# Sheet2.net
KiCad netlist of a schematic drawn in Altium Designer
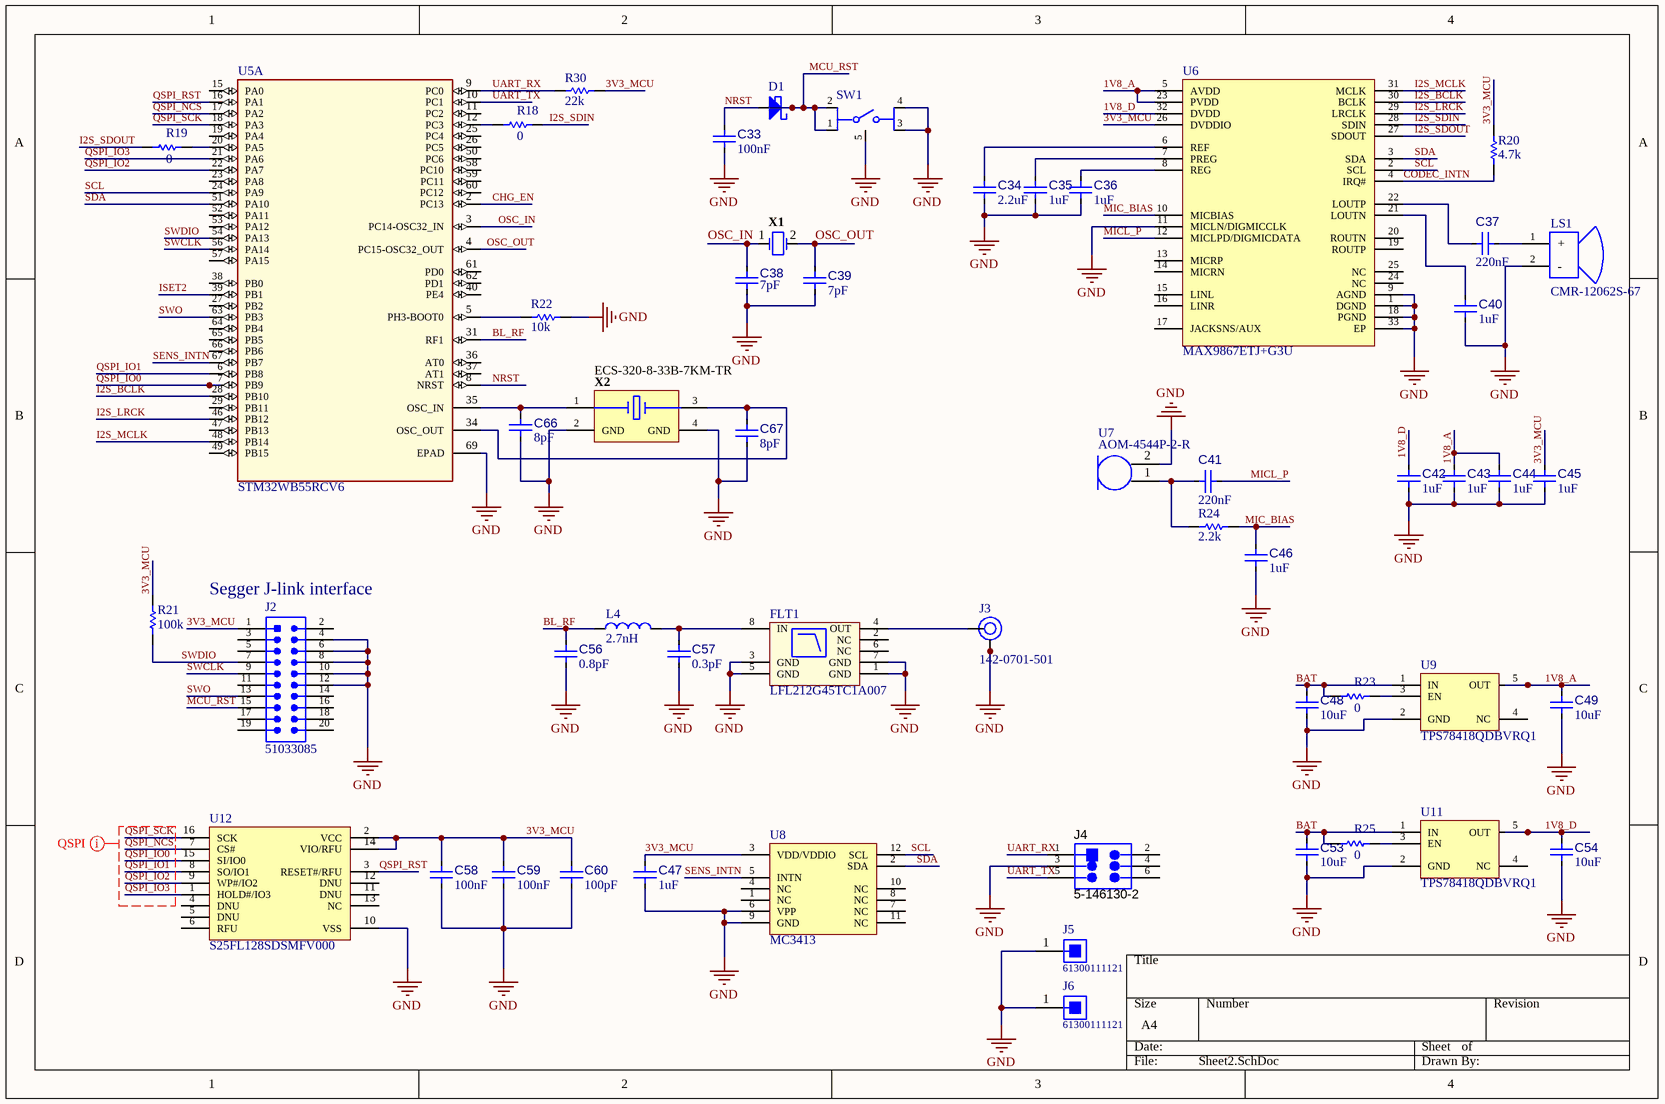
[diagram p0: Sheet2.SchDoc]

(export (version "E")
  (design (tool "Eeschema 10.0.6"))
  (components
    (comp (ref "C33")
      (value "100nF")
      (footprint "0402-SMD-CAP")
      (description "Chip Capacitor, 0.1 uF, +/- 5%, 16 V, 0402 (1005 Metric)")
      (fields (field (name "TOLERANCE") "5%") (field (name "MFR. PART NO.") "EMF105B7104MVHF"))
      (libsource (lib "Budapest University of Technology and Economics") (part "CAP-NP-2"))
    )
    (comp (ref "C34")
      (value "2.2uF")
      (footprint "0603-SMD-CAP")
      (description "CAP CER 2.2UF 10V X7R 0603")
      (fields (field (name "TOLERANCE") "10%") (field (name "VOLTAGE") "10V"))
      (libsource (lib "Budapest University of Technology and Economics") (part "CAP-NP-2"))
    )
    (comp (ref "C35")
      (value "1uF")
      (footprint "0603-SMD-CAP")
      (fields
        (field (name "VOLTAGE") "25V")
        (field (name "TOLERANCE") "10%")
        (field (name "MFR. PART NO.") "C0603C105K3PACTU")
      )
      (libsource (lib "Budapest University of Technology and Economics") (part "CAP-NP-2"))
    )
    (comp (ref "C36")
      (value "1uF")
      (footprint "0603-SMD-CAP")
      (fields
        (field (name "VOLTAGE") "25V")
        (field (name "TOLERANCE") "10%")
        (field (name "MFR. PART NO.") "C0603C105K3PACTU")
      )
      (libsource (lib "Budapest University of Technology and Economics") (part "CAP-NP-2"))
    )
    (comp (ref "C37")
      (value "220nF")
      (footprint "0402-SMD-CAP")
      (fields
        (field (name "VOLTAGE") "16V")
        (field (name "TOLERANCE") "10%")
        (field (name "Comment") "GRM155R71C224KA12D")
      )
      (libsource (lib "Budapest University of Technology and Economics") (part "CAP-NP-2"))
    )
    (comp (ref "C38")
      (value "7pF")
      (footprint "0402-SMD-CAP")
      (description "Cap Ceramic 7pF 50V C0G 0.25pF SMD 0402 125C T/R")
      (fields (field (name "MFR. PART NO.") "04025A7R0CAT2A") (field (name "VOLTAGE") "50V"))
      (libsource (lib "Budapest University of Technology and Economics") (part "CAP-NP-2"))
    )
    (comp (ref "C39")
      (value "7pF")
      (footprint "0402-SMD-CAP")
      (description "Cap Ceramic 7pF 50V C0G 0.25pF SMD 0402 125C T/R")
      (fields (field (name "MFR. PART NO.") "04025A7R0CAT2A") (field (name "VOLTAGE") "50V"))
      (libsource (lib "Budapest University of Technology and Economics") (part "CAP-NP-2"))
    )
    (comp (ref "C40")
      (value "1uF")
      (footprint "0603-SMD-CAP")
      (fields
        (field (name "VOLTAGE") "25V")
        (field (name "TOLERANCE") "10%")
        (field (name "MFR. PART NO.") "C0603C105K3PACTU")
      )
      (libsource (lib "Budapest University of Technology and Economics") (part "CAP-NP-2"))
    )
    (comp (ref "C41")
      (value "220nF")
      (footprint "0402-SMD-CAP")
      (fields
        (field (name "VOLTAGE") "16V")
        (field (name "TOLERANCE") "10%")
        (field (name "Comment") "GRM155R71C224KA12D")
      )
      (libsource (lib "Budapest University of Technology and Economics") (part "CAP-NP-2"))
    )
    (comp (ref "C42")
      (value "1uF")
      (footprint "0603-SMD-CAP")
      (fields
        (field (name "VOLTAGE") "25V")
        (field (name "TOLERANCE") "10%")
        (field (name "MFR. PART NO.") "C0603C105K3PACTU")
      )
      (libsource (lib "Budapest University of Technology and Economics") (part "CAP-NP-2"))
    )
    (comp (ref "C43")
      (value "1uF")
      (footprint "0603-SMD-CAP")
      (fields
        (field (name "VOLTAGE") "25V")
        (field (name "TOLERANCE") "10%")
        (field (name "MFR. PART NO.") "C0603C105K3PACTU")
      )
      (libsource (lib "Budapest University of Technology and Economics") (part "CAP-NP-2"))
    )
    (comp (ref "C44")
      (value "1uF")
      (footprint "0603-SMD-CAP")
      (fields
        (field (name "VOLTAGE") "25V")
        (field (name "TOLERANCE") "10%")
        (field (name "MFR. PART NO.") "C0603C105K3PACTU")
      )
      (libsource (lib "Budapest University of Technology and Economics") (part "CAP-NP-2"))
    )
    (comp (ref "C45")
      (value "1uF")
      (footprint "0603-SMD-CAP")
      (fields
        (field (name "VOLTAGE") "25V")
        (field (name "TOLERANCE") "10%")
        (field (name "MFR. PART NO.") "C0603C105K3PACTU")
      )
      (libsource (lib "Budapest University of Technology and Economics") (part "CAP-NP-2"))
    )
    (comp (ref "C46")
      (value "1uF")
      (footprint "0603-SMD-CAP")
      (fields
        (field (name "VOLTAGE") "25V")
        (field (name "TOLERANCE") "10%")
        (field (name "MFR. PART NO.") "C0603C105K3PACTU")
      )
      (libsource (lib "Budapest University of Technology and Economics") (part "CAP-NP-2"))
    )
    (comp (ref "C47")
      (value "1uF")
      (footprint "0603-SMD-CAP")
      (fields
        (field (name "VOLTAGE") "25V")
        (field (name "TOLERANCE") "10%")
        (field (name "MFR. PART NO.") "C0603C105K3PACTU")
      )
      (libsource (lib "Budapest University of Technology and Economics") (part "CAP-NP-2"))
    )
    (comp (ref "C48")
      (value "10uF")
      (footprint "0805-SMD-CAP")
      (description "CAP CER 10UF 10V X5R 0805")
      (fields (field (name "TOLERANCE") "10%") (field (name "VOLTAGE") "10V"))
      (libsource (lib "Budapest University of Technology and Economics") (part "CAP-NP-2"))
    )
    (comp (ref "C49")
      (value "10uF")
      (footprint "0805-SMD-CAP")
      (description "CAP CER 10UF 10V X5R 0805")
      (fields (field (name "TOLERANCE") "10%") (field (name "VOLTAGE") "10V"))
      (libsource (lib "Budapest University of Technology and Economics") (part "CAP-NP-2"))
    )
    (comp (ref "C53")
      (value "10uF")
      (footprint "0805-SMD-CAP")
      (description "CAP CER 10UF 10V X5R 0805")
      (fields (field (name "TOLERANCE") "10%") (field (name "VOLTAGE") "10V"))
      (libsource (lib "Budapest University of Technology and Economics") (part "CAP-NP-2"))
    )
    (comp (ref "C54")
      (value "10uF")
      (footprint "0805-SMD-CAP")
      (description "CAP CER 10UF 10V X5R 0805")
      (fields (field (name "TOLERANCE") "10%") (field (name "VOLTAGE") "10V"))
      (libsource (lib "Budapest University of Technology and Economics") (part "CAP-NP-2"))
    )
    (comp (ref "C56")
      (value "0.8pF")
      (footprint "0402-SMD-CAP")
      (description "Cap Ceramic 0.8pF 50V C0G 0.1pF SMD 0402 125C Paper T/R")
      (fields (field (name "MFR. PART NO.") "GJM1555C1HR80BB01D") (field (name "VOLTAGE") "50V"))
      (libsource (lib "Budapest University of Technology and Economics") (part "CAP-NP-2"))
    )
    (comp (ref "C57")
      (value "0.3pF")
      (footprint "0402-SMD-CAP")
      (description "Multilayer Ceramic Capacitors MLCC - SMD/SMT 0402 0.3pF 50Volts C0G +/-0.05pF")
      (fields (field (name "MFR. PART NO.") "GJM1555C1HR30WB01D"))
      (libsource (lib "Budapest University of Technology and Economics") (part "CAP-NP-2"))
    )
    (comp (ref "C58")
      (value "100nF")
      (footprint "0603-SMD-CAP")
      (description "CAPACITOR CERAMIC, 0.1UF, 50V, X7R, 10%, 0603")
      (fields (field (name "TOLERANCE") "10%") (field (name "MFR. PART NO.") "CC0603KRX7R9BB104"))
      (libsource (lib "Budapest University of Technology and Economics") (part "CAP-NP-2"))
    )
    (comp (ref "C59")
      (value "100nF")
      (footprint "0603-SMD-CAP")
      (description "CAPACITOR CERAMIC, 0.1UF, 50V, X7R, 10%, 0603")
      (fields (field (name "TOLERANCE") "10%") (field (name "MFR. PART NO.") "CC0603KRX7R9BB104"))
      (libsource (lib "Budapest University of Technology and Economics") (part "CAP-NP-2"))
    )
    (comp (ref "C60")
      (value "100pF")
      (footprint "0402-SMD-CAP")
      (description "Capacitor, Ceramic; 100pf; Chip; Case 0402; Npo; +/-5%; 50wvdc; Smd; 2.5% Df; Tr")
      (fields (field (name "VOLTAGE") "50V") (field (name "TOLERANCE") "5%"))
      (libsource (lib "Budapest University of Technology and Economics") (part "CAP-NP-2"))
    )
    (comp (ref "C66")
      (value "8pF")
      (footprint "0402-SMD-CAP")
      (fields (field (name "MFR. PART NO.") "CGA2B2C0G1H080D050BA"))
      (libsource (lib "Budapest University of Technology and Economics") (part "CAP-NP-2"))
    )
    (comp (ref "C67")
      (value "8pF")
      (footprint "0402-SMD-CAP")
      (fields (field (name "MFR. PART NO.") "CGA2B2C0G1H080D050BA"))
      (libsource (lib "Budapest University of Technology and Economics") (part "CAP-NP-2"))
    )
    (comp (ref "D1")
      (value "SS12-E3/61T")
      (footprint "VISH-DO-214AC_V")
      (description "Schottky Barrier Rectifier, 20 V, 1 A, -65 to 150 degC, 2-Pin DO-214AC (SMA), RoHS, Tape and Reel")
      (fields (field (name "MANUFACTURER") "Vishay Semiconductor"))
      (libsource (lib "Budapest University of Technology and Economics") (part "DSKY-AK-2"))
    )
    (comp (ref "FLT1")
      (value "LFL212G45TC1A007")
      (footprint "LFL212G45TC1A007-Footprint-1")
      (description "CHIP MULTILAYER LC FILTER")
      (libsource (lib "Budapest University of Technology and Economics") (part "LFL212G45TC1A007"))
    )
    (comp (ref "J2")
      (value "51033085")
      (footprint "51033085-Footprint-1")
      (description "CONN HEADER VERT 20POS 2.54MM")
      (libsource (lib "Budapest University of Technology and Economics") (part "CN-2P-M-R20"))
    )
    (comp (ref "J3")
      (value "142-0701-501")
      (footprint "142-0701-501-Footprint-1")
      (description "CONN SMA JACK R/A 50 OHM PCB")
      (libsource (lib "Budapest University of Technology and Economics") (part "SMA"))
    )
    (comp (ref "J4")
      (value "5-146130-2")
      (footprint "TECO-5-146130-2_V")
      (description "Male Header, Pitch 2.54 mm, 2 x 3 Position, Height 8.13 mm, -65 to 125 degC, RoHS, Tube")
      (fields (field (name "MANUFACTURER") "TE Connectivity"))
      (libsource (lib "Budapest University of Technology and Economics") (part "CN-2P-M-R6"))
    )
    (comp (ref "J5")
      (value "61300111121")
      (footprint "61300111121")
      (description "CONN HEADER VERT 1POS")
      (libsource (lib "Budapest University of Technology and Economics") (part "WE-CN-1P-M-R1"))
    )
    (comp (ref "J6")
      (value "61300111121")
      (footprint "61300111121")
      (description "CONN HEADER VERT 1POS")
      (libsource (lib "Budapest University of Technology and Economics") (part "WE-CN-1P-M-R1"))
    )
    (comp (ref "L4")
      (value "LQG15HS2N7S02D")
      (footprint "0402-SMD-IND")
      (description "MURATA - LQG15HS2N7S02D - INDUCTOR, 2.7NH, 0.8A, 0402, MULTILAYER")
      (fields (field (name "INDUCTANCE") "2.7nH"))
      (libsource (lib "Budapest University of Technology and Economics") (part "IND-2"))
    )
    (comp (ref "LS1")
      (value "CMR-12062S-67")
      (footprint "CMR-12062S-67-Footprint-1")
      (description "SPEAKER, 12 X 6 MM, 2 MM DEEP, M")
      (fields (field (name "MANUFACTURER") "CUI Devices"))
      (libsource (lib "Budapest University of Technology and Economics") (part "SPEAKER-2"))
    )
    (comp (ref "R18")
      (value "0")
      (footprint "0603-SMD-RES")
      (description "Jumper 0603")
      (libsource (lib "Budapest University of Technology and Economics") (part "RES-2"))
    )
    (comp (ref "R19")
      (value "0")
      (footprint "0603-SMD-RES")
      (description "Jumper 0603")
      (libsource (lib "Budapest University of Technology and Economics") (part "RES-2"))
    )
    (comp (ref "R20")
      (value "4.7k")
      (footprint "0603-SMD-RES")
      (description "RESISTOR, 0603, 0.1W, 1%, 4K7")
      (fields (field (name "TOLERANCE") "1%") (field (name "Comment") "ERJ-3EKF4701V"))
      (libsource (lib "Budapest University of Technology and Economics") (part "RES-2"))
    )
    (comp (ref "R21")
      (value "100k")
      (footprint "0603-SMD-RES")
      (description "Chip Resistor, 100 KOhm, +/- 1%, 0.1 W, -55 to 155 degC, 0603 (1608 Metric)")
      (fields (field (name "TOLERANCE") "1%") (field (name "POWER") "100mW"))
      (libsource (lib "Budapest University of Technology and Economics") (part "RES-2"))
    )
    (comp (ref "R22")
      (value "10k")
      (footprint "0402_SMD_RES")
      (description "Chip Resistor, 10 kOhms, +/-1 %, 63 mW, -55 to 125 degC, 0402")
      (fields (field (name "POWER") "63mW") (field (name "MFR. PART NO.") "CRCW040210K0FKTD"))
      (libsource (lib "Budapest University of Technology and Economics") (part "RES-2"))
    )
    (comp (ref "R23")
      (value "0")
      (footprint "0603-SMD-RES")
      (description "Jumper 0603")
      (libsource (lib "Budapest University of Technology and Economics") (part "RES-2"))
    )
    (comp (ref "R24")
      (value "2.2k")
      (footprint "0603-SMD-RES")
      (description "SMD Resistor, Thick film 2.2 kOhm,  ±  1 %, 0603, CRCW06032K20FKEA, Vishay")
      (fields (field (name "TOLERANCE") "1%") (field (name "MFR. PART NO.") "CRCW06032K20FKEA"))
      (libsource (lib "Budapest University of Technology and Economics") (part "RES-2"))
    )
    (comp (ref "R25")
      (value "0")
      (footprint "0603-SMD-RES")
      (description "Jumper 0603")
      (libsource (lib "Budapest University of Technology and Economics") (part "RES-2"))
    )
    (comp (ref "R30")
      (value "22k")
      (footprint "0603-SMD-RES")
      (fields (field (name "TOLERANCE") "1%") (field (name "Comment") "CRCW060322K0FKEA"))
      (libsource (lib "Budapest University of Technology and Economics") (part "RES-2"))
    )
    (comp (ref "SW1")
      (value "KMR231GLFS")
      (footprint "FP-KMR231GLFS-MFG")
      (description "Switch Tactile N.O. SPST Button Gull Wing 0.05A 32VDC 1VA 150000Cycles 3N SMD T/R")
      (libsource (lib "Budapest University of Technology and Economics") (part "9acf178d7dd3ac41aa24a061361ece5"))
    )
    (comp (ref "U5")
      (value "STM32WB55RCV6")
      (footprint "QFN40P800X800X100_HS-69N")
      (fields (field (name "MANUFACTURER") "ST"))
      (libsource (lib "Budapest University of Technology and Economics") (part "STM32WB55RCV6"))
    )
    (comp (ref "U6")
      (value "MAX9867ETJ+G3U")
      (footprint "QFN50P500X500X80_HS-33N")
      (description "MAX9867 Series 1.8V I2C/Serial Ultra-Low Power Stereo Audio Codec - TQFN-32EP")
      (libsource (lib "Budapest University of Technology and Economics") (part "MAX9867ETJ+G3U"))
    )
    (comp (ref "U7")
      (value "AOM-4544P-2-R")
      (footprint "AOM-4544P-2-R-Footprint-1")
      (description "Microphones 2.2K OHM 9.7mm")
      (libsource (lib "Budapest University of Technology and Economics") (part "AOM-4544P-2-R-Symbol-1"))
    )
    (comp (ref "U8")
      (value "MC3413")
      (footprint "MC3413 -Footprint-1")
      (description "3-AXIS Iomt Accelerometer (1.6X1")
      (fields (field (name "MANUFACTURER") "MEMSIC"))
      (libsource (lib "Budapest University of Technology and Economics") (part "MC3413"))
    )
    (comp (ref "U9")
      (value "TPS78418QDBVRQ1")
      (footprint "SOT23127P600-8N")
      (fields (field (name "MANUFACTURER") "Texas Instruments"))
      (libsource (lib "Budapest University of Technology and Economics") (part "TPS784XXQDBVRQ1"))
    )
    (comp (ref "U11")
      (value "TPS78418QDBVRQ1")
      (footprint "SOT23127P600-8N")
      (fields (field (name "MANUFACTURER") "Texas Instruments"))
      (libsource (lib "Budapest University of Technology and Economics") (part "TPS784XXQDBVRQ1"))
    )
    (comp (ref "U12")
      (value "S25FL128SDSMFV000")
      (footprint "SOIC127P1030X265-16M")
      (description "128-MBIT Cmos 3.0 Volt Flash Memory With 80MHZ Ddr Spi (ser")
      (fields (field (name "MFR. PART NO.") "S25FL128SDSMFV001"))
      (libsource (lib "Budapest University of Technology and Economics") (part "S25FL128SDSMFV001"))
    )
    (comp (ref "X1")
      (value "ECS-.327-7-12-TR")
      (footprint "ECS-.327-7-12-TR-Footprint-1")
      (description "CRYSTAL 32.7680KHZ 7PF SMD")
      (libsource (lib "Budapest University of Technology and Economics") (part "XTAL-1-2-2"))
    )
    (comp (ref "X2")
      (value "ECS-320-8-33B-7KM-TR")
      (footprint "ECS-320-8-33B-7KM-TR-Footprint-1")
      (description "Crystal 32MHz ±7ppm (Tol) ±10ppm (Stability) 8pF FUND 40Ohm 4-Pin Mini-CSMD T/R")
      (fields (field (name "TOLERANCE") "7ppm"))
      (libsource (lib "Budapest University of Technology and Economics") (part "XTAL-1-3-4"))
    )
  )
  (nets
    (net (code "1") (name "/1V8_A") (class "Default")
      (node (ref "C43") (pin "1") (pinfunction "1_1") (pintype "passive"))
      (node (ref "C44") (pin "1") (pinfunction "1_1") (pintype "passive"))
      (node (ref "C49") (pin "1") (pinfunction "1_1") (pintype "passive"))
      (node (ref "U6") (pin "23") (pinfunction "PVDD_23") (pintype "passive"))
      (node (ref "U6") (pin "5") (pinfunction "AVDD_5") (pintype "passive"))
      (node (ref "U9") (pin "5") (pinfunction "OUT_5") (pintype "power_in"))
    )
    (net (code "2") (name "/1V8_D") (class "Default")
      (node (ref "C42") (pin "1") (pinfunction "1_1") (pintype "passive"))
      (node (ref "C54") (pin "1") (pinfunction "1_1") (pintype "passive"))
      (node (ref "U11") (pin "5") (pinfunction "OUT_5") (pintype "power_in"))
      (node (ref "U6") (pin "32") (pinfunction "DVDD_32") (pintype "passive"))
    )
    (net (code "3") (name "/3V3_MCU") (class "Default")
      (node (ref "C45") (pin "1") (pinfunction "1_1") (pintype "passive"))
      (node (ref "C47") (pin "1") (pinfunction "1_1") (pintype "passive"))
      (node (ref "C58") (pin "1") (pinfunction "1_1") (pintype "passive"))
      (node (ref "C59") (pin "1") (pinfunction "1_1") (pintype "passive"))
      (node (ref "C60") (pin "1") (pinfunction "1_1") (pintype "passive"))
      (node (ref "J2") (pin "1") (pinfunction "1_1") (pintype "passive"))
      (node (ref "R20") (pin "2") (pinfunction "2_2") (pintype "passive"))
      (node (ref "R21") (pin "2") (pinfunction "2_2") (pintype "passive"))
      (node (ref "R30") (pin "1") (pinfunction "1_1") (pintype "passive"))
      (node (ref "U12") (pin "14") (pinfunction "VIO/RFU_14") (pintype "passive"))
      (node (ref "U12") (pin "2") (pinfunction "VCC_2") (pintype "passive"))
      (node (ref "U6") (pin "26") (pinfunction "DVDDIO_26") (pintype "passive"))
      (node (ref "U8") (pin "3") (pinfunction "VDD/VDDIO_3") (pintype "passive"))
    )
    (net (code "4") (name "/BAT") (class "Default")
      (node (ref "C48") (pin "1") (pinfunction "1_1") (pintype "passive"))
      (node (ref "C53") (pin "1") (pinfunction "1_1") (pintype "passive"))
      (node (ref "R23") (pin "1") (pinfunction "1_1") (pintype "passive"))
      (node (ref "R25") (pin "1") (pinfunction "1_1") (pintype "passive"))
      (node (ref "U11") (pin "1") (pinfunction "IN_1") (pintype "power_in"))
      (node (ref "U9") (pin "1") (pinfunction "IN_1") (pintype "power_in"))
    )
    (net (code "5") (name "/BL_RF") (class "Default")
      (node (ref "C56") (pin "1") (pinfunction "1_1") (pintype "passive"))
      (node (ref "L4") (pin "1") (pinfunction "1_1") (pintype "passive"))
      (node (ref "U5") (pin "31") (pinfunction "RF1_31") (pintype "bidirectional"))
    )
    (net (code "6") (name "/CHG_EN") (class "Default")
      (node (ref "U5") (pin "2") (pinfunction "PC13_2") (pintype "bidirectional"))
    )
    (net (code "7") (name "/CODEC_INTN") (class "Default")
      (node (ref "R20") (pin "1") (pinfunction "1_1") (pintype "passive"))
      (node (ref "U6") (pin "4") (pinfunction "IRQ#_4") (pintype "passive"))
    )
    (net (code "8") (name "/I2S_BCLK") (class "Default")
      (node (ref "U5") (pin "28") (pinfunction "PB10_28") (pintype "bidirectional"))
      (node (ref "U6") (pin "30") (pinfunction "BCLK_30") (pintype "passive"))
    )
    (net (code "9") (name "/I2S_LRCK") (class "Default")
      (node (ref "U5") (pin "46") (pinfunction "PB12_46") (pintype "bidirectional"))
      (node (ref "U6") (pin "29") (pinfunction "LRCLK_29") (pintype "passive"))
    )
    (net (code "10") (name "/I2S_MCLK") (class "Default")
      (node (ref "U5") (pin "48") (pinfunction "PB14_48") (pintype "bidirectional"))
      (node (ref "U6") (pin "31") (pinfunction "MCLK_31") (pintype "passive"))
    )
    (net (code "11") (name "/I2S_SDIN") (class "Default")
      (node (ref "R18") (pin "2") (pinfunction "2_2") (pintype "passive"))
      (node (ref "U6") (pin "28") (pinfunction "SDIN_28") (pintype "passive"))
    )
    (net (code "12") (name "/I2S_SDOUT") (class "Default")
      (node (ref "R19") (pin "1") (pinfunction "1_1") (pintype "passive"))
      (node (ref "U6") (pin "27") (pinfunction "SDOUT_27") (pintype "passive"))
    )
    (net (code "13") (name "/ISET2") (class "Default")
      (node (ref "U5") (pin "39") (pinfunction "PB1_39") (pintype "bidirectional"))
    )
    (net (code "14") (name "/MCU_RST") (class "Default")
      (node (ref "D1") (pin "2") (pinfunction "K_2") (pintype "passive"))
      (node (ref "J2") (pin "15") (pinfunction "15_15") (pintype "passive"))
      (node (ref "SW1") (pin "1") (pinfunction "1_1") (pintype "passive"))
      (node (ref "SW1") (pin "2") (pinfunction "2_2") (pintype "passive"))
    )
    (net (code "15") (name "/MICL_P") (class "Default")
      (node (ref "C41") (pin "2") (pinfunction "2_2") (pintype "passive"))
      (node (ref "U6") (pin "12") (pinfunction "MICLPD/DIGMICDATA_12") (pintype "passive"))
    )
    (net (code "16") (name "/MIC_BIAS") (class "Default")
      (node (ref "C46") (pin "1") (pinfunction "1_1") (pintype "passive"))
      (node (ref "R24") (pin "2") (pinfunction "2_2") (pintype "passive"))
      (node (ref "U6") (pin "10") (pinfunction "MICBIAS_10") (pintype "passive"))
    )
    (net (code "17") (name "/NRST") (class "Default")
      (node (ref "C33") (pin "1") (pinfunction "1_1") (pintype "passive"))
      (node (ref "D1") (pin "1") (pinfunction "A_1") (pintype "passive"))
      (node (ref "U5") (pin "8") (pinfunction "NRST_8") (pintype "bidirectional"))
    )
    (net (code "18") (name "/OSC_IN") (class "Default")
      (node (ref "C38") (pin "2") (pinfunction "2_2") (pintype "passive"))
      (node (ref "U5") (pin "3") (pinfunction "PC14-OSC32_IN_3") (pintype "bidirectional"))
      (node (ref "X1") (pin "1") (pinfunction "1_1") (pintype "passive"))
    )
    (net (code "19") (name "/OSC_OUT") (class "Default")
      (node (ref "C39") (pin "2") (pinfunction "2_2") (pintype "passive"))
      (node (ref "U5") (pin "4") (pinfunction "PC15-OSC32_OUT_4") (pintype "bidirectional"))
      (node (ref "X1") (pin "2") (pinfunction "2_2") (pintype "passive"))
    )
    (net (code "20") (name "/QSPI_IO0") (class "Default")
      (node (ref "U12") (pin "15") (pinfunction "SI/IO0_15") (pintype "passive"))
      (node (ref "U5") (pin "7") (pinfunction "PB9_7") (pintype "bidirectional"))
    )
    (net (code "21") (name "/QSPI_IO1") (class "Default")
      (node (ref "U12") (pin "8") (pinfunction "SO/IO1_8") (pintype "passive"))
      (node (ref "U5") (pin "6") (pinfunction "PB8_6") (pintype "bidirectional"))
    )
    (net (code "22") (name "/QSPI_IO2") (class "Default")
      (node (ref "U12") (pin "9") (pinfunction "WP#/IO2_9") (pintype "passive"))
      (node (ref "U5") (pin "22") (pinfunction "PA7_22") (pintype "bidirectional"))
    )
    (net (code "23") (name "/QSPI_IO3") (class "Default")
      (node (ref "U12") (pin "1") (pinfunction "HOLD#/IO3_1") (pintype "passive"))
      (node (ref "U5") (pin "21") (pinfunction "PA6_21") (pintype "bidirectional"))
    )
    (net (code "24") (name "/QSPI_NCS") (class "Default")
      (node (ref "U12") (pin "7") (pinfunction "CS#_7") (pintype "passive"))
      (node (ref "U5") (pin "17") (pinfunction "PA2_17") (pintype "bidirectional"))
    )
    (net (code "25") (name "/QSPI_RST") (class "Default")
      (node (ref "U12") (pin "3") (pinfunction "RESET#/RFU_3") (pintype "passive"))
      (node (ref "U5") (pin "16") (pinfunction "PA1_16") (pintype "bidirectional"))
    )
    (net (code "26") (name "/QSPI_SCK") (class "Default")
      (node (ref "U12") (pin "16") (pinfunction "SCK_16") (pintype "passive"))
      (node (ref "U5") (pin "18") (pinfunction "PA3_18") (pintype "bidirectional"))
    )
    (net (code "27") (name "/SCL") (class "Default")
      (node (ref "U5") (pin "24") (pinfunction "PA9_24") (pintype "bidirectional"))
      (node (ref "U6") (pin "2") (pinfunction "SCL_2") (pintype "passive"))
      (node (ref "U8") (pin "12") (pinfunction "SCL_12") (pintype "passive"))
    )
    (net (code "28") (name "/SDA") (class "Default")
      (node (ref "U5") (pin "51") (pinfunction "PA10_51") (pintype "bidirectional"))
      (node (ref "U6") (pin "3") (pinfunction "SDA_3") (pintype "passive"))
      (node (ref "U8") (pin "2") (pinfunction "SDA_2") (pintype "passive"))
    )
    (net (code "29") (name "/SENS_INTN") (class "Default")
      (node (ref "U5") (pin "67") (pinfunction "PB7_67") (pintype "bidirectional"))
      (node (ref "U8") (pin "5") (pinfunction "INTN_5") (pintype "passive"))
    )
    (net (code "30") (name "/SWCLK") (class "Default")
      (node (ref "J2") (pin "9") (pinfunction "9_9") (pintype "passive"))
      (node (ref "U5") (pin "56") (pinfunction "PA14_56") (pintype "bidirectional"))
    )
    (net (code "31") (name "/SWDIO") (class "Default")
      (node (ref "J2") (pin "7") (pinfunction "7_7") (pintype "passive"))
      (node (ref "R21") (pin "1") (pinfunction "1_1") (pintype "passive"))
      (node (ref "U5") (pin "54") (pinfunction "PA13_54") (pintype "bidirectional"))
    )
    (net (code "32") (name "/SWO") (class "Default")
      (node (ref "J2") (pin "13") (pinfunction "13_13") (pintype "passive"))
      (node (ref "U5") (pin "63") (pinfunction "PB3_63") (pintype "bidirectional"))
    )
    (net (code "33") (name "/UART_RX") (class "Default")
      (node (ref "J4") (pin "1") (pinfunction "1_1") (pintype "passive"))
      (node (ref "R30") (pin "2") (pinfunction "2_2") (pintype "passive"))
      (node (ref "U5") (pin "9") (pinfunction "PC0_9") (pintype "bidirectional"))
    )
    (net (code "34") (name "/UART_TX") (class "Default")
      (node (ref "J4") (pin "5") (pinfunction "5_5") (pintype "passive"))
      (node (ref "U5") (pin "10") (pinfunction "PC1_10") (pintype "bidirectional"))
    )
    (net (code "35") (name "GND") (class "Default")
      (node (ref "C33") (pin "2") (pinfunction "2_2") (pintype "passive"))
      (node (ref "C34") (pin "2") (pinfunction "2_2") (pintype "passive"))
      (node (ref "C35") (pin "2") (pinfunction "2_2") (pintype "passive"))
      (node (ref "C36") (pin "2") (pinfunction "2_2") (pintype "passive"))
      (node (ref "C38") (pin "1") (pinfunction "1_1") (pintype "passive"))
      (node (ref "C39") (pin "1") (pinfunction "1_1") (pintype "passive"))
      (node (ref "C40") (pin "2") (pinfunction "2_2") (pintype "passive"))
      (node (ref "C42") (pin "2") (pinfunction "2_2") (pintype "passive"))
      (node (ref "C43") (pin "2") (pinfunction "2_2") (pintype "passive"))
      (node (ref "C44") (pin "2") (pinfunction "2_2") (pintype "passive"))
      (node (ref "C45") (pin "2") (pinfunction "2_2") (pintype "passive"))
      (node (ref "C46") (pin "2") (pinfunction "2_2") (pintype "passive"))
      (node (ref "C47") (pin "2") (pinfunction "2_2") (pintype "passive"))
      (node (ref "C48") (pin "2") (pinfunction "2_2") (pintype "passive"))
      (node (ref "C49") (pin "2") (pinfunction "2_2") (pintype "passive"))
      (node (ref "C53") (pin "2") (pinfunction "2_2") (pintype "passive"))
      (node (ref "C54") (pin "2") (pinfunction "2_2") (pintype "passive"))
      (node (ref "C56") (pin "2") (pinfunction "2_2") (pintype "passive"))
      (node (ref "C57") (pin "2") (pinfunction "2_2") (pintype "passive"))
      (node (ref "C58") (pin "2") (pinfunction "2_2") (pintype "passive"))
      (node (ref "C59") (pin "2") (pinfunction "2_2") (pintype "passive"))
      (node (ref "C60") (pin "2") (pinfunction "2_2") (pintype "passive"))
      (node (ref "C66") (pin "2") (pinfunction "2_2") (pintype "passive"))
      (node (ref "C67") (pin "2") (pinfunction "2_2") (pintype "passive"))
      (node (ref "FLT1") (pin "1") (pinfunction "GND_1") (pintype "passive"))
      (node (ref "FLT1") (pin "3") (pinfunction "GND_3") (pintype "passive"))
      (node (ref "FLT1") (pin "5") (pinfunction "GND_5") (pintype "passive"))
      (node (ref "FLT1") (pin "7") (pinfunction "GND_7") (pintype "passive"))
      (node (ref "J2") (pin "10") (pinfunction "10_10") (pintype "passive"))
      (node (ref "J2") (pin "12") (pinfunction "12_12") (pintype "passive"))
      (node (ref "J2") (pin "4") (pinfunction "4_4") (pintype "passive"))
      (node (ref "J2") (pin "6") (pinfunction "6_6") (pintype "passive"))
      (node (ref "J2") (pin "8") (pinfunction "8_8") (pintype "passive"))
      (node (ref "J3") (pin "2") (pinfunction "2_2") (pintype "power_in"))
      (node (ref "J3") (pin "3") (pinfunction "3_3") (pintype "power_in"))
      (node (ref "J3") (pin "4") (pinfunction "1_4") (pintype "power_in"))
      (node (ref "J3") (pin "5") (pinfunction "4_5") (pintype "power_in"))
      (node (ref "J4") (pin "3") (pinfunction "3_3") (pintype "passive"))
      (node (ref "J5") (pin "1") (pinfunction "1_1") (pintype "passive"))
      (node (ref "J6") (pin "1") (pinfunction "1_1") (pintype "passive"))
      (node (ref "LS1") (pin "2") (pinfunction "-_2") (pintype "passive"))
      (node (ref "R22") (pin "1") (pinfunction "1_1") (pintype "passive"))
      (node (ref "SW1") (pin "3") (pinfunction "3_3") (pintype "passive"))
      (node (ref "SW1") (pin "4") (pinfunction "4_4") (pintype "passive"))
      (node (ref "SW1") (pin "5") (pinfunction "GND_5") (pintype "power_in"))
      (node (ref "U11") (pin "2") (pinfunction "GND_2") (pintype "power_in"))
      (node (ref "U12") (pin "10") (pinfunction "VSS_10") (pintype "passive"))
      (node (ref "U5") (pin "69") (pinfunction "EPAD_69") (pintype "passive"))
      (node (ref "U6") (pin "1") (pinfunction "DGND_1") (pintype "passive"))
      (node (ref "U6") (pin "11") (pinfunction "MICLN/DIGMICCLK_11") (pintype "passive"))
      (node (ref "U6") (pin "18") (pinfunction "PGND_18") (pintype "passive"))
      (node (ref "U6") (pin "33") (pinfunction "EP_33") (pintype "passive"))
      (node (ref "U6") (pin "9") (pinfunction "AGND_9") (pintype "passive"))
      (node (ref "U7") (pin "2") (pinfunction "-_2") (pintype "passive"))
      (node (ref "U8") (pin "6") (pinfunction "VPP_6") (pintype "passive"))
      (node (ref "U8") (pin "9") (pinfunction "GND_9") (pintype "passive"))
      (node (ref "U9") (pin "2") (pinfunction "GND_2") (pintype "power_in"))
      (node (ref "X2") (pin "2") (pinfunction "GND_2") (pintype "power_in"))
      (node (ref "X2") (pin "4") (pinfunction "GND_4") (pintype "power_in"))
    )
    (net (code "36") (name "Net-(FLT1-IN)") (class "Default")
      (node (ref "C57") (pin "1") (pinfunction "1_1") (pintype "passive"))
      (node (ref "FLT1") (pin "8") (pinfunction "IN_8") (pintype "passive"))
      (node (ref "L4") (pin "2") (pinfunction "2_2") (pintype "passive"))
    )
    (net (code "37") (name "Net-(FLT1-OUT)") (class "Default")
      (node (ref "FLT1") (pin "4") (pinfunction "OUT_4") (pintype "passive"))
      (node (ref "J3") (pin "1") (pinfunction "0_1") (pintype "passive"))
    )
    (net (code "38") (name "Net-(LS1-+)") (class "Default")
      (node (ref "C37") (pin "2") (pinfunction "2_2") (pintype "passive"))
      (node (ref "LS1") (pin "1") (pinfunction "+_1") (pintype "passive"))
    )
    (net (code "39") (name "Net-(U5A-OSC_IN)") (class "Default")
      (node (ref "C66") (pin "1") (pinfunction "1_1") (pintype "passive"))
      (node (ref "U5") (pin "35") (pinfunction "OSC_IN_35") (pintype "passive"))
      (node (ref "X2") (pin "1") (pinfunction "X1_1") (pintype "passive"))
    )
    (net (code "40") (name "Net-(U5A-OSC_OUT)") (class "Default")
      (node (ref "C67") (pin "1") (pinfunction "1_1") (pintype "passive"))
      (node (ref "U5") (pin "34") (pinfunction "OSC_OUT_34") (pintype "passive"))
      (node (ref "X2") (pin "3") (pinfunction "X2_3") (pintype "passive"))
    )
    (net (code "41") (name "Net-(U5A-PA5)") (class "Default")
      (node (ref "R19") (pin "2") (pinfunction "2_2") (pintype "passive"))
      (node (ref "U5") (pin "20") (pinfunction "PA5_20") (pintype "bidirectional"))
    )
    (net (code "42") (name "Net-(U5A-PC3)") (class "Default")
      (node (ref "R18") (pin "1") (pinfunction "1_1") (pintype "passive"))
      (node (ref "U5") (pin "12") (pinfunction "PC3_12") (pintype "bidirectional"))
    )
    (net (code "43") (name "Net-(U5A-PH3-BOOT0)") (class "Default")
      (node (ref "R22") (pin "2") (pinfunction "2_2") (pintype "passive"))
      (node (ref "U5") (pin "5") (pinfunction "PH3-BOOT0_5") (pintype "bidirectional"))
    )
    (net (code "44") (name "Net-(U6-LOUTN)") (class "Default")
      (node (ref "C40") (pin "1") (pinfunction "1_1") (pintype "passive"))
      (node (ref "U6") (pin "21") (pinfunction "LOUTN_21") (pintype "passive"))
    )
    (net (code "45") (name "Net-(U6-LOUTP)") (class "Default")
      (node (ref "C37") (pin "1") (pinfunction "1_1") (pintype "passive"))
      (node (ref "U6") (pin "22") (pinfunction "LOUTP_22") (pintype "passive"))
    )
    (net (code "46") (name "Net-(U6-PREG)") (class "Default")
      (node (ref "C35") (pin "1") (pinfunction "1_1") (pintype "passive"))
      (node (ref "U6") (pin "7") (pinfunction "PREG_7") (pintype "passive"))
    )
    (net (code "47") (name "Net-(U6-REF)") (class "Default")
      (node (ref "C34") (pin "1") (pinfunction "1_1") (pintype "passive"))
      (node (ref "U6") (pin "6") (pinfunction "REF_6") (pintype "passive"))
    )
    (net (code "48") (name "Net-(U6-REG)") (class "Default")
      (node (ref "C36") (pin "1") (pinfunction "1_1") (pintype "passive"))
      (node (ref "U6") (pin "8") (pinfunction "REG_8") (pintype "passive"))
    )
    (net (code "49") (name "Net-(U7-+)") (class "Default")
      (node (ref "C41") (pin "1") (pinfunction "1_1") (pintype "passive"))
      (node (ref "R24") (pin "1") (pinfunction "1_1") (pintype "passive"))
      (node (ref "U7") (pin "1") (pinfunction "+_1") (pintype "passive"))
    )
    (net (code "50") (name "Net-(U9-EN)") (class "Default")
      (node (ref "R23") (pin "2") (pinfunction "2_2") (pintype "passive"))
      (node (ref "U9") (pin "3") (pinfunction "EN_3") (pintype "power_in"))
    )
    (net (code "51") (name "Net-(U11-EN)") (class "Default")
      (node (ref "R25") (pin "2") (pinfunction "2_2") (pintype "passive"))
      (node (ref "U11") (pin "3") (pinfunction "EN_3") (pintype "power_in"))
    )
    (net (code "52") (name "unconnected-(FLT1-NC-Pad2)") (class "Default")
      (node (ref "FLT1") (pin "2") (pinfunction "NC_2") (pintype "passive"))
    )
    (net (code "53") (name "unconnected-(FLT1-NC-Pad6)") (class "Default")
      (node (ref "FLT1") (pin "6") (pinfunction "NC_6") (pintype "passive"))
    )
    (net (code "54") (name "unconnected-(J2-Pad2)") (class "Default")
      (node (ref "J2") (pin "2") (pinfunction "2_2") (pintype "passive"))
    )
    (net (code "55") (name "unconnected-(J2-Pad3)") (class "Default")
      (node (ref "J2") (pin "3") (pinfunction "3_3") (pintype "passive"))
    )
    (net (code "56") (name "unconnected-(J2-Pad5)") (class "Default")
      (node (ref "J2") (pin "5") (pinfunction "5_5") (pintype "passive"))
    )
    (net (code "57") (name "unconnected-(J2-Pad11)") (class "Default")
      (node (ref "J2") (pin "11") (pinfunction "11_11") (pintype "passive"))
    )
    (net (code "58") (name "unconnected-(J2-Pad14)") (class "Default")
      (node (ref "J2") (pin "14") (pinfunction "14_14") (pintype "passive"))
    )
    (net (code "59") (name "unconnected-(J2-Pad16)") (class "Default")
      (node (ref "J2") (pin "16") (pinfunction "16_16") (pintype "passive"))
    )
    (net (code "60") (name "unconnected-(J2-Pad17)") (class "Default")
      (node (ref "J2") (pin "17") (pinfunction "17_17") (pintype "passive"))
    )
    (net (code "61") (name "unconnected-(J2-Pad18)") (class "Default")
      (node (ref "J2") (pin "18") (pinfunction "18_18") (pintype "passive"))
    )
    (net (code "62") (name "unconnected-(J2-Pad19)") (class "Default")
      (node (ref "J2") (pin "19") (pinfunction "19_19") (pintype "passive"))
    )
    (net (code "63") (name "unconnected-(J2-Pad20)") (class "Default")
      (node (ref "J2") (pin "20") (pinfunction "20_20") (pintype "passive"))
    )
    (net (code "64") (name "unconnected-(J4-Pad2)") (class "Default")
      (node (ref "J4") (pin "2") (pinfunction "2_2") (pintype "passive"))
    )
    (net (code "65") (name "unconnected-(J4-Pad4)") (class "Default")
      (node (ref "J4") (pin "4") (pinfunction "4_4") (pintype "passive"))
    )
    (net (code "66") (name "unconnected-(J4-Pad6)") (class "Default")
      (node (ref "J4") (pin "6") (pinfunction "6_6") (pintype "passive"))
    )
    (net (code "67") (name "unconnected-(U5A-AT0-Pad36)") (class "Default")
      (node (ref "U5") (pin "36") (pinfunction "AT0_36") (pintype "bidirectional"))
    )
    (net (code "68") (name "unconnected-(U5A-AT1-Pad37)") (class "Default")
      (node (ref "U5") (pin "37") (pinfunction "AT1_37") (pintype "bidirectional"))
    )
    (net (code "69") (name "unconnected-(U5A-PA0-Pad15)") (class "Default")
      (node (ref "U5") (pin "15") (pinfunction "PA0_15") (pintype "bidirectional"))
    )
    (net (code "70") (name "unconnected-(U5A-PA4-Pad19)") (class "Default")
      (node (ref "U5") (pin "19") (pinfunction "PA4_19") (pintype "bidirectional"))
    )
    (net (code "71") (name "unconnected-(U5A-PA8-Pad23)") (class "Default")
      (node (ref "U5") (pin "23") (pinfunction "PA8_23") (pintype "bidirectional"))
    )
    (net (code "72") (name "unconnected-(U5A-PA11-Pad52)") (class "Default")
      (node (ref "U5") (pin "52") (pinfunction "PA11_52") (pintype "bidirectional"))
    )
    (net (code "73") (name "unconnected-(U5A-PA12-Pad53)") (class "Default")
      (node (ref "U5") (pin "53") (pinfunction "PA12_53") (pintype "bidirectional"))
    )
    (net (code "74") (name "unconnected-(U5A-PA15-Pad57)") (class "Default")
      (node (ref "U5") (pin "57") (pinfunction "PA15_57") (pintype "bidirectional"))
    )
    (net (code "75") (name "unconnected-(U5A-PB0-Pad38)") (class "Default")
      (node (ref "U5") (pin "38") (pinfunction "PB0_38") (pintype "bidirectional"))
    )
    (net (code "76") (name "unconnected-(U5A-PB2-Pad27)") (class "Default")
      (node (ref "U5") (pin "27") (pinfunction "PB2_27") (pintype "bidirectional"))
    )
    (net (code "77") (name "unconnected-(U5A-PB4-Pad64)") (class "Default")
      (node (ref "U5") (pin "64") (pinfunction "PB4_64") (pintype "bidirectional"))
    )
    (net (code "78") (name "unconnected-(U5A-PB5-Pad65)") (class "Default")
      (node (ref "U5") (pin "65") (pinfunction "PB5_65") (pintype "bidirectional"))
    )
    (net (code "79") (name "unconnected-(U5A-PB6-Pad66)") (class "Default")
      (node (ref "U5") (pin "66") (pinfunction "PB6_66") (pintype "bidirectional"))
    )
    (net (code "80") (name "unconnected-(U5A-PB11-Pad29)") (class "Default")
      (node (ref "U5") (pin "29") (pinfunction "PB11_29") (pintype "bidirectional"))
    )
    (net (code "81") (name "unconnected-(U5A-PB13-Pad47)") (class "Default")
      (node (ref "U5") (pin "47") (pinfunction "PB13_47") (pintype "bidirectional"))
    )
    (net (code "82") (name "unconnected-(U5A-PB15-Pad49)") (class "Default")
      (node (ref "U5") (pin "49") (pinfunction "PB15_49") (pintype "bidirectional"))
    )
    (net (code "83") (name "unconnected-(U5A-PC2-Pad11)") (class "Default")
      (node (ref "U5") (pin "11") (pinfunction "PC2_11") (pintype "bidirectional"))
    )
    (net (code "84") (name "unconnected-(U5A-PC4-Pad25)") (class "Default")
      (node (ref "U5") (pin "25") (pinfunction "PC4_25") (pintype "bidirectional"))
    )
    (net (code "85") (name "unconnected-(U5A-PC5-Pad26)") (class "Default")
      (node (ref "U5") (pin "26") (pinfunction "PC5_26") (pintype "bidirectional"))
    )
    (net (code "86") (name "unconnected-(U5A-PC6-Pad50)") (class "Default")
      (node (ref "U5") (pin "50") (pinfunction "PC6_50") (pintype "bidirectional"))
    )
    (net (code "87") (name "unconnected-(U5A-PC10-Pad58)") (class "Default")
      (node (ref "U5") (pin "58") (pinfunction "PC10_58") (pintype "bidirectional"))
    )
    (net (code "88") (name "unconnected-(U5A-PC11-Pad59)") (class "Default")
      (node (ref "U5") (pin "59") (pinfunction "PC11_59") (pintype "bidirectional"))
    )
    (net (code "89") (name "unconnected-(U5A-PC12-Pad60)") (class "Default")
      (node (ref "U5") (pin "60") (pinfunction "PC12_60") (pintype "bidirectional"))
    )
    (net (code "90") (name "unconnected-(U5A-PD0-Pad61)") (class "Default")
      (node (ref "U5") (pin "61") (pinfunction "PD0_61") (pintype "bidirectional"))
    )
    (net (code "91") (name "unconnected-(U5A-PD1-Pad62)") (class "Default")
      (node (ref "U5") (pin "62") (pinfunction "PD1_62") (pintype "bidirectional"))
    )
    (net (code "92") (name "unconnected-(U5A-PE4-Pad40)") (class "Default")
      (node (ref "U5") (pin "40") (pinfunction "PE4_40") (pintype "bidirectional"))
    )
    (net (code "93") (name "unconnected-(U6-JACKSNS{slash}AUX-Pad17)") (class "Default")
      (node (ref "U6") (pin "17") (pinfunction "JACKSNS/AUX_17") (pintype "passive"))
    )
    (net (code "94") (name "unconnected-(U6-LINL-Pad15)") (class "Default")
      (node (ref "U6") (pin "15") (pinfunction "LINL_15") (pintype "passive"))
    )
    (net (code "95") (name "unconnected-(U6-LINR-Pad16)") (class "Default")
      (node (ref "U6") (pin "16") (pinfunction "LINR_16") (pintype "passive"))
    )
    (net (code "96") (name "unconnected-(U6-MICRN-Pad14)") (class "Default")
      (node (ref "U6") (pin "14") (pinfunction "MICRN_14") (pintype "passive"))
    )
    (net (code "97") (name "unconnected-(U6-MICRP-Pad13)") (class "Default")
      (node (ref "U6") (pin "13") (pinfunction "MICRP_13") (pintype "passive"))
    )
    (net (code "98") (name "unconnected-(U6-NC-Pad24)") (class "Default")
      (node (ref "U6") (pin "24") (pinfunction "NC_24") (pintype "passive"))
    )
    (net (code "99") (name "unconnected-(U6-NC-Pad25)") (class "Default")
      (node (ref "U6") (pin "25") (pinfunction "NC_25") (pintype "passive"))
    )
    (net (code "100") (name "unconnected-(U6-ROUTN-Pad20)") (class "Default")
      (node (ref "U6") (pin "20") (pinfunction "ROUTN_20") (pintype "passive"))
    )
    (net (code "101") (name "unconnected-(U6-ROUTP-Pad19)") (class "Default")
      (node (ref "U6") (pin "19") (pinfunction "ROUTP_19") (pintype "passive"))
    )
    (net (code "102") (name "unconnected-(U8-NC-Pad1)") (class "Default")
      (node (ref "U8") (pin "1") (pinfunction "NC_1") (pintype "passive"))
    )
    (net (code "103") (name "unconnected-(U8-NC-Pad4)") (class "Default")
      (node (ref "U8") (pin "4") (pinfunction "NC_4") (pintype "passive"))
    )
    (net (code "104") (name "unconnected-(U8-NC-Pad7)") (class "Default")
      (node (ref "U8") (pin "7") (pinfunction "NC_7") (pintype "passive"))
    )
    (net (code "105") (name "unconnected-(U8-NC-Pad8)") (class "Default")
      (node (ref "U8") (pin "8") (pinfunction "NC_8") (pintype "passive"))
    )
    (net (code "106") (name "unconnected-(U8-NC-Pad10)") (class "Default")
      (node (ref "U8") (pin "10") (pinfunction "NC_10") (pintype "passive"))
    )
    (net (code "107") (name "unconnected-(U8-NC-Pad11)") (class "Default")
      (node (ref "U8") (pin "11") (pinfunction "NC_11") (pintype "passive"))
    )
    (net (code "108") (name "unconnected-(U9-NC-Pad4)") (class "Default")
      (node (ref "U9") (pin "4") (pinfunction "NC_4") (pintype "power_in"))
    )
    (net (code "109") (name "unconnected-(U11-NC-Pad4)") (class "Default")
      (node (ref "U11") (pin "4") (pinfunction "NC_4") (pintype "power_in"))
    )
    (net (code "110") (name "unconnected-(U12-DNU-Pad4)") (class "Default")
      (node (ref "U12") (pin "4") (pinfunction "DNU_4") (pintype "passive"))
    )
    (net (code "111") (name "unconnected-(U12-DNU-Pad5)") (class "Default")
      (node (ref "U12") (pin "5") (pinfunction "DNU_5") (pintype "passive"))
    )
    (net (code "112") (name "unconnected-(U12-DNU-Pad11)") (class "Default")
      (node (ref "U12") (pin "11") (pinfunction "DNU_11") (pintype "passive"))
    )
    (net (code "113") (name "unconnected-(U12-DNU-Pad12)") (class "Default")
      (node (ref "U12") (pin "12") (pinfunction "DNU_12") (pintype "passive"))
    )
    (net (code "114") (name "unconnected-(U12-NC-Pad13)") (class "Default")
      (node (ref "U12") (pin "13") (pinfunction "NC_13") (pintype "passive"))
    )
    (net (code "115") (name "unconnected-(U12-RFU-Pad6)") (class "Default")
      (node (ref "U12") (pin "6") (pinfunction "RFU_6") (pintype "passive"))
    )
  )
)
